# BuildUpons-CenterLED.net
KiCad netlist of a schematic drawn in EAGLE
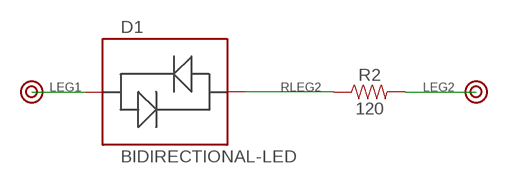
[diagram p0: schematic, sheet 1]

(export (version "E")
  (design (tool "Eeschema 10.0.6"))
  (components
    (comp (ref "D1")
      (value "BIDIRECTIONAL-LED")
      (footprint "eagle-import:BIDIRECTIONAL-LED")
      (libsource (lib "eagle-import") (part "BIDIRECTIONAL-LED"))
    )
    (comp (ref "J1")
      (value "METAL-LEGMOREPASTE")
      (footprint "eagle-import:METAL-LEG")
      (libsource (lib "eagle-import") (part "METAL-LEGMOREPASTE"))
    )
    (comp (ref "J2")
      (value "METAL-LEGMOREPASTE")
      (footprint "eagle-import:METAL-LEG")
      (libsource (lib "eagle-import") (part "METAL-LEGMOREPASTE"))
    )
    (comp (ref "R2")
      (value "120")
      (footprint "eagle-import:0402")
      (libsource (lib "eagle-import") (part "RESISTOR1"))
    )
  )
  (nets
    (net (code "1") (name "/LEG1") (class "Default")
      (node (ref "D1") (pin "LED1") (pinfunction "LED1_LED1") (pintype "bidirectional"))
      (node (ref "J1") (pin "1") (pinfunction "PIN1_1") (pintype "bidirectional"))
    )
    (net (code "2") (name "/LEG2") (class "Default")
      (node (ref "J2") (pin "1") (pinfunction "PIN1_1") (pintype "bidirectional"))
      (node (ref "R2") (pin "2") (pinfunction "2_2") (pintype "passive"))
    )
    (net (code "3") (name "/RLEG2") (class "Default")
      (node (ref "D1") (pin "LED2") (pinfunction "LED2_LED2") (pintype "bidirectional"))
      (node (ref "R2") (pin "1") (pinfunction "1_1") (pintype "passive"))
    )
  )
)
